# Sheet1.net
KiCad netlist of a schematic drawn in Altium Designer
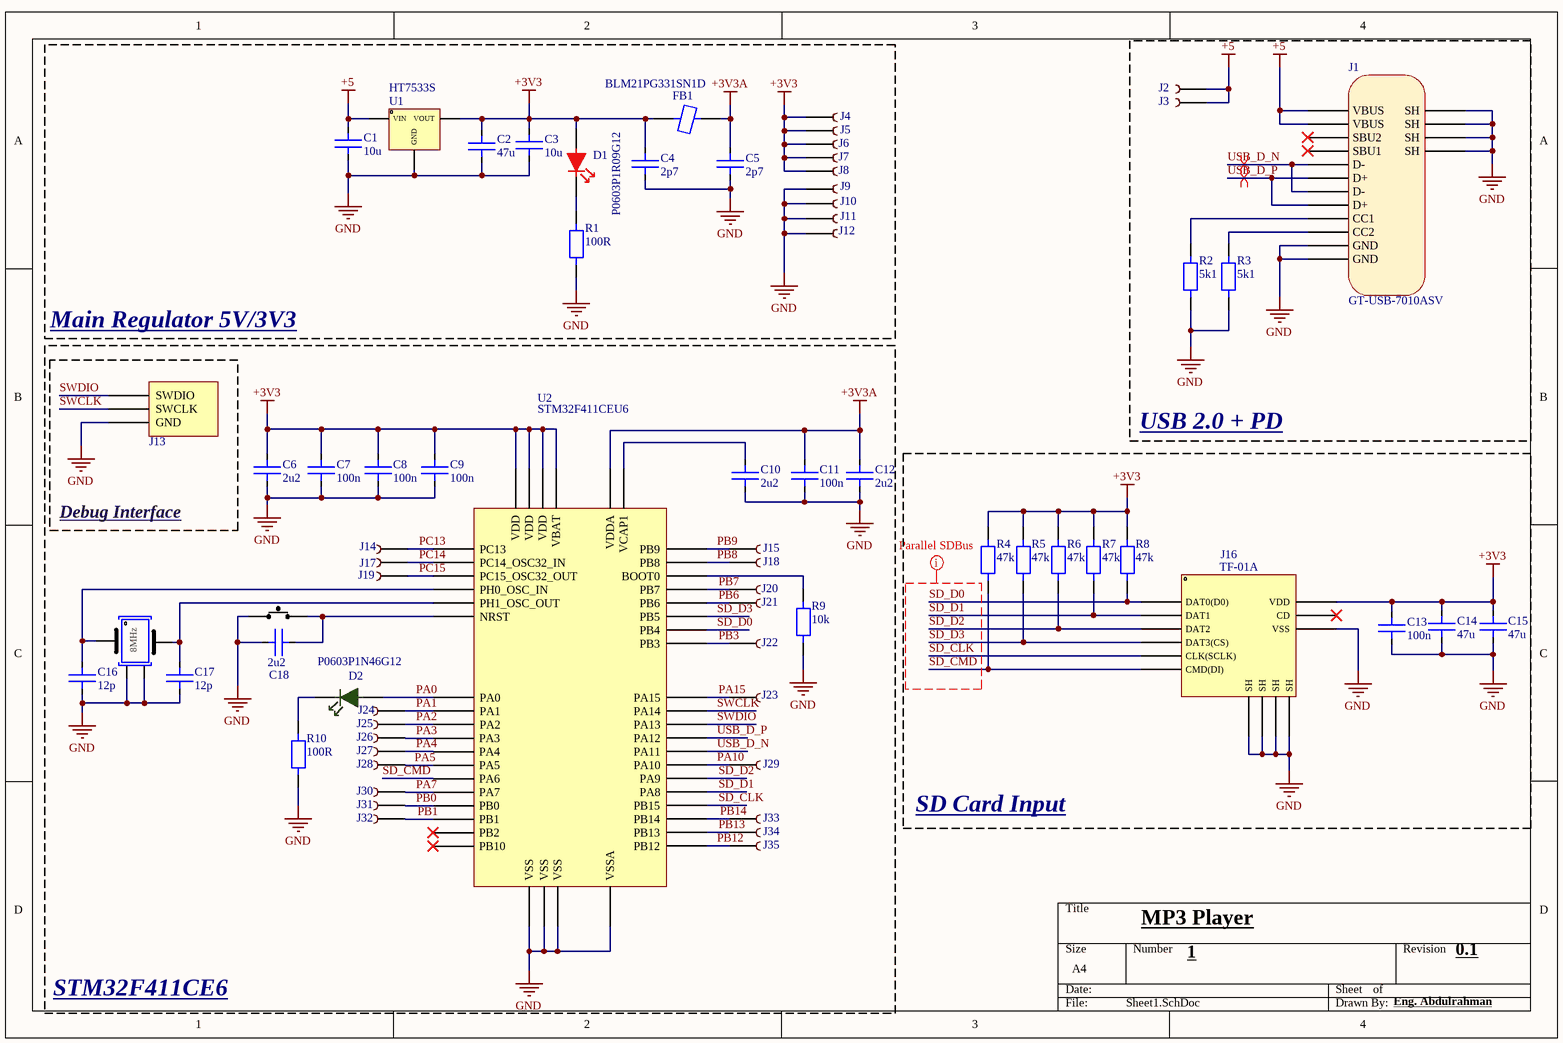
[diagram p0: Sheet1.SchDoc]

(export (version "E")
  (design (tool "Eeschema 10.0.6"))
  (components
    (comp (ref "C1")
      (value "10u")
      (footprint "CAP_MLCC_0805")
      (description "Multilayer  Ceramic Capacitor")
      (libsource (lib "conics_libs") (part "Cap MLCC 0805"))
    )
    (comp (ref "C2")
      (value "47u")
      (footprint "CAP_MLCC_0805")
      (description "Multilayer  Ceramic Capacitor")
      (libsource (lib "conics_libs") (part "Cap MLCC 0805"))
    )
    (comp (ref "C3")
      (value "10u")
      (footprint "CAP_MLCC_0805")
      (description "Multilayer  Ceramic Capacitor")
      (libsource (lib "conics_libs") (part "Cap MLCC 0805"))
    )
    (comp (ref "C4")
      (value "2p7")
      (footprint "CAP_MLCC_0402")
      (description "Multilayer  Ceramic Capacitor")
      (libsource (lib "conics_libs") (part "Cap MLCC 0402"))
    )
    (comp (ref "C5")
      (value "2p7")
      (footprint "CAP_MLCC_0402")
      (description "Multilayer  Ceramic Capacitor")
      (libsource (lib "conics_libs") (part "Cap MLCC 0402"))
    )
    (comp (ref "C6")
      (value "2u2")
      (footprint "CAP_MLCC_0402")
      (description "Multilayer  Ceramic Capacitor")
      (libsource (lib "conics_libs") (part "Cap MLCC 0402"))
    )
    (comp (ref "C7")
      (value "100n")
      (footprint "CAP_MLCC_0402")
      (description "Multilayer  Ceramic Capacitor")
      (libsource (lib "conics_libs") (part "Cap MLCC 0402"))
    )
    (comp (ref "C8")
      (value "100n")
      (footprint "CAP_MLCC_0402")
      (description "Multilayer  Ceramic Capacitor")
      (libsource (lib "conics_libs") (part "Cap MLCC 0402"))
    )
    (comp (ref "C9")
      (value "100n")
      (footprint "CAP_MLCC_0402")
      (description "Multilayer  Ceramic Capacitor")
      (libsource (lib "conics_libs") (part "Cap MLCC 0402"))
    )
    (comp (ref "C10")
      (value "2u2")
      (footprint "CAP_MLCC_0402")
      (description "Multilayer  Ceramic Capacitor")
      (libsource (lib "conics_libs") (part "Cap MLCC 0402"))
    )
    (comp (ref "C11")
      (value "100n")
      (footprint "CAP_MLCC_0402")
      (description "Multilayer  Ceramic Capacitor")
      (libsource (lib "conics_libs") (part "Cap MLCC 0402"))
    )
    (comp (ref "C12")
      (value "2u2")
      (footprint "CAP_MLCC_0402")
      (description "Multilayer  Ceramic Capacitor")
      (libsource (lib "conics_libs") (part "Cap MLCC 0402"))
    )
    (comp (ref "C13")
      (value "100n")
      (footprint "CAP_MLCC_0402")
      (description "Multilayer  Ceramic Capacitor")
      (libsource (lib "conics_libs") (part "Cap MLCC 0402"))
    )
    (comp (ref "C14")
      (value "47u")
      (footprint "CAP_MLCC_0805")
      (description "Multilayer  Ceramic Capacitor")
      (libsource (lib "conics_libs") (part "Cap MLCC 0805"))
    )
    (comp (ref "C15")
      (value "47u")
      (footprint "CAP_MLCC_0805")
      (description "Multilayer  Ceramic Capacitor")
      (libsource (lib "conics_libs") (part "Cap MLCC 0805"))
    )
    (comp (ref "C16")
      (value "12p")
      (footprint "CAP_MLCC_0402")
      (description "Multilayer  Ceramic Capacitor")
      (libsource (lib "conics_libs") (part "Cap MLCC 0402"))
    )
    (comp (ref "C17")
      (value "12p")
      (footprint "CAP_MLCC_0402")
      (description "Multilayer  Ceramic Capacitor")
      (libsource (lib "conics_libs") (part "Cap MLCC 0402"))
    )
    (comp (ref "C18")
      (value "2u2")
      (footprint "CAP_MLCC_0402")
      (description "Multilayer  Ceramic Capacitor")
      (libsource (lib "conics_libs") (part "Cap MLCC 0402"))
    )
    (comp (ref "D1")
      (value "P0603P1R09G12")
      (footprint "LED_0603")
      (description "20mA 350mcd 621nm Red 2V 0603 LED Indication - Discrete ROHS")
      (libsource (lib "conics_libs") (part "Diode LED R"))
    )
    (comp (ref "D2")
      (value "P0603P1N46G12")
      (footprint "LED_0603")
      (description "1200mcd 518nm~524nm Green 3V 0603 LED Indication - Discrete ROHS")
      (libsource (lib "conics_libs") (part "Diode LED G"))
    )
    (comp (ref "FB1")
      (value "BLM21PG331SN1D")
      (footprint "FBEAD_0805")
      (description "70mΩ ±25% 330Ω@100MHz 0805 Ferrite Beads and Chips RoHS")
      (libsource (lib "conics_libs") (part "Filter Ferrite Bead 0805"))
    )
    (comp (ref "J1")
      (value "GT-USB-7010ASV")
      (footprint "CONN_CH_USB_SMD_USB")
      (description "USB 2.0 1 16P -40℃~+85℃ Type-C SMD USB, DVI, HDMI Connector Assemblies ROHS")
      (libsource (lib "conics_libs") (part "Connector USB-C CH"))
    )
    (comp (ref "J2")
      (value "Castellated Pad")
      (footprint "CPad")
      (libsource (lib "conics_libs") (part "Castellated Pad"))
    )
    (comp (ref "J3")
      (value "Castellated Pad")
      (footprint "CPad")
      (libsource (lib "conics_libs") (part "Castellated Pad"))
    )
    (comp (ref "J4")
      (value "Castellated Pad")
      (footprint "CPad")
      (libsource (lib "conics_libs") (part "Castellated Pad"))
    )
    (comp (ref "J5")
      (value "Castellated Pad")
      (footprint "CPad")
      (libsource (lib "conics_libs") (part "Castellated Pad"))
    )
    (comp (ref "J6")
      (value "Castellated Pad")
      (footprint "CPad")
      (libsource (lib "conics_libs") (part "Castellated Pad"))
    )
    (comp (ref "J7")
      (value "Castellated Pad")
      (footprint "CPad")
      (libsource (lib "conics_libs") (part "Castellated Pad"))
    )
    (comp (ref "J8")
      (value "Castellated Pad")
      (footprint "CPad")
      (libsource (lib "conics_libs") (part "Castellated Pad"))
    )
    (comp (ref "J9")
      (value "Castellated Pad")
      (footprint "CPad")
      (libsource (lib "conics_libs") (part "Castellated Pad"))
    )
    (comp (ref "J10")
      (value "Castellated Pad")
      (footprint "CPad")
      (libsource (lib "conics_libs") (part "Castellated Pad"))
    )
    (comp (ref "J11")
      (value "Castellated Pad")
      (footprint "CPad")
      (libsource (lib "conics_libs") (part "Castellated Pad"))
    )
    (comp (ref "J12")
      (value "Castellated Pad")
      (footprint "CPad")
      (libsource (lib "conics_libs") (part "Castellated Pad"))
    )
    (comp (ref "J13")
      (value "DAP SWD")
      (footprint "CONN_JST_3P")
      (description "Connector Header 3 position 1mm Pitch 1A Surface Mount,Vertical -25℃~+85℃")
      (libsource (lib "conics_libs") (part "DAP SWD"))
    )
    (comp (ref "J14")
      (value "Castellated Pad")
      (footprint "CPad")
      (libsource (lib "conics_libs") (part "Castellated Pad"))
    )
    (comp (ref "J15")
      (value "Castellated Pad")
      (footprint "CPad")
      (libsource (lib "conics_libs") (part "Castellated Pad"))
    )
    (comp (ref "J16")
      (value "TF-01A")
      (footprint "CONN_CH_SMD_SD_CARD")
      (description "Push-Push 1.85mm Connector and Ejector MicroSD Card (TF Card) SMD PC Card Sockets ROHS")
      (libsource (lib "conics_libs") (part "Connector SD Card CH"))
    )
    (comp (ref "J17")
      (value "Castellated Pad")
      (footprint "CPad")
      (libsource (lib "conics_libs") (part "Castellated Pad"))
    )
    (comp (ref "J18")
      (value "Castellated Pad")
      (footprint "CPad")
      (libsource (lib "conics_libs") (part "Castellated Pad"))
    )
    (comp (ref "J19")
      (value "Castellated Pad")
      (footprint "CPad")
      (libsource (lib "conics_libs") (part "Castellated Pad"))
    )
    (comp (ref "J20")
      (value "Castellated Pad")
      (footprint "CPad")
      (libsource (lib "conics_libs") (part "Castellated Pad"))
    )
    (comp (ref "J21")
      (value "Castellated Pad")
      (footprint "CPad")
      (libsource (lib "conics_libs") (part "Castellated Pad"))
    )
    (comp (ref "J22")
      (value "Castellated Pad")
      (footprint "CPad")
      (libsource (lib "conics_libs") (part "Castellated Pad"))
    )
    (comp (ref "J23")
      (value "Castellated Pad")
      (footprint "CPad")
      (libsource (lib "conics_libs") (part "Castellated Pad"))
    )
    (comp (ref "J24")
      (value "Castellated Pad")
      (footprint "CPad")
      (libsource (lib "conics_libs") (part "Castellated Pad"))
    )
    (comp (ref "J25")
      (value "Castellated Pad")
      (footprint "CPad")
      (libsource (lib "conics_libs") (part "Castellated Pad"))
    )
    (comp (ref "J26")
      (value "Castellated Pad")
      (footprint "CPad")
      (libsource (lib "conics_libs") (part "Castellated Pad"))
    )
    (comp (ref "J27")
      (value "Castellated Pad")
      (footprint "CPad")
      (libsource (lib "conics_libs") (part "Castellated Pad"))
    )
    (comp (ref "J28")
      (value "Castellated Pad")
      (footprint "CPad")
      (libsource (lib "conics_libs") (part "Castellated Pad"))
    )
    (comp (ref "J29")
      (value "Castellated Pad")
      (footprint "CPad")
      (libsource (lib "conics_libs") (part "Castellated Pad"))
    )
    (comp (ref "J30")
      (value "Castellated Pad")
      (footprint "CPad")
      (libsource (lib "conics_libs") (part "Castellated Pad"))
    )
    (comp (ref "J31")
      (value "Castellated Pad")
      (footprint "CPad")
      (libsource (lib "conics_libs") (part "Castellated Pad"))
    )
    (comp (ref "J32")
      (value "Castellated Pad")
      (footprint "CPad")
      (libsource (lib "conics_libs") (part "Castellated Pad"))
    )
    (comp (ref "J33")
      (value "Castellated Pad")
      (footprint "CPad")
      (libsource (lib "conics_libs") (part "Castellated Pad"))
    )
    (comp (ref "J34")
      (value "Castellated Pad")
      (footprint "CPad")
      (libsource (lib "conics_libs") (part "Castellated Pad"))
    )
    (comp (ref "J35")
      (value "Castellated Pad")
      (footprint "CPad")
      (libsource (lib "conics_libs") (part "Castellated Pad"))
    )
    (comp (ref "R1")
      (value "100R")
      (footprint "RES_SMD_0402")
      (description "General Purpose SMD Carbon Resistor")
      (libsource (lib "conics_libs") (part "Resistor 0402"))
    )
    (comp (ref "R2")
      (value "5k1")
      (footprint "RES_SMD_0402")
      (description "General Purpose SMD Carbon Resistor")
      (libsource (lib "conics_libs") (part "Resistor 0402"))
    )
    (comp (ref "R3")
      (value "5k1")
      (footprint "RES_SMD_0402")
      (description "General Purpose SMD Carbon Resistor")
      (libsource (lib "conics_libs") (part "Resistor 0402"))
    )
    (comp (ref "R4")
      (value "47k")
      (footprint "RES_SMD_0402")
      (description "General Purpose SMD Carbon Resistor")
      (libsource (lib "conics_libs") (part "Resistor 0402"))
    )
    (comp (ref "R5")
      (value "47k")
      (footprint "RES_SMD_0402")
      (description "General Purpose SMD Carbon Resistor")
      (libsource (lib "conics_libs") (part "Resistor 0402"))
    )
    (comp (ref "R6")
      (value "47k")
      (footprint "RES_SMD_0402")
      (description "General Purpose SMD Carbon Resistor")
      (libsource (lib "conics_libs") (part "Resistor 0402"))
    )
    (comp (ref "R7")
      (value "47k")
      (footprint "RES_SMD_0402")
      (description "General Purpose SMD Carbon Resistor")
      (libsource (lib "conics_libs") (part "Resistor 0402"))
    )
    (comp (ref "R8")
      (value "47k")
      (footprint "RES_SMD_0402")
      (description "General Purpose SMD Carbon Resistor")
      (libsource (lib "conics_libs") (part "Resistor 0402"))
    )
    (comp (ref "R9")
      (value "10k")
      (footprint "RES_SMD_0402")
      (description "General Purpose SMD Carbon Resistor")
      (libsource (lib "conics_libs") (part "Resistor 0402"))
    )
    (comp (ref "R10")
      (value "100R")
      (footprint "RES_SMD_0402")
      (description "General Purpose SMD Carbon Resistor")
      (libsource (lib "conics_libs") (part "Resistor 0402"))
    )
    (comp (ref "SW1")
      (value "TS-1088-AR02016")
      (footprint "SW_SMD_SPST")
      (description "Without Bracket 4mm 12V 3mm Round Button SPST 50mA SMD,4x3mm Tactile Switches ROHS")
      (libsource (lib "conics_libs") (part "Switch SMD SPST"))
    )
    (comp (ref "U1")
      (value "HT7533S")
      (footprint "HT7533S_SOT23")
      (description "Linear Voltage Regulator IC Positive Fixed 1 Output 100mA SOT-23")
      (libsource (lib "conics_libs") (part "Regulator LDO HT7533S"))
    )
    (comp (ref "U2")
      (value "STM32F411CEU6")
      (footprint "STM32F411CEU6_QFPN48")
      (description "ARM Cortex-M4 32 Bit 100MHz 36 UFQFPN-48(7x7) Microcontrollers RoHS")
      (libsource (lib "conics_libs") (part "MCU STM32F411CEU6"))
    )
    (comp (ref "X1")
      (value "XC32M4-8.000-F12LJDT")
      (footprint "XTAL_SMD_HCL")
      (description "Crystal Oscillator 12pF SMD3225-4P Crystals RoHS")
      (libsource (lib "conics_libs") (part "Crystal SMD 8MHz"))
    )
  )
  (nets
    (net (code "1") (name "+3V3") (class "Default")
      (node (ref "C13") (pin "2") (pintype "passive"))
      (node (ref "C14") (pin "2") (pintype "passive"))
      (node (ref "C15") (pin "2") (pintype "passive"))
      (node (ref "C2") (pin "2") (pintype "passive"))
      (node (ref "C3") (pin "2") (pintype "passive"))
      (node (ref "C4") (pin "2") (pintype "passive"))
      (node (ref "C6") (pin "2") (pintype "passive"))
      (node (ref "C7") (pin "2") (pintype "passive"))
      (node (ref "C8") (pin "2") (pintype "passive"))
      (node (ref "C9") (pin "2") (pintype "passive"))
      (node (ref "D1") (pin "2") (pintype "passive"))
      (node (ref "FB1") (pin "1") (pintype "passive"))
      (node (ref "J16") (pin "4") (pinfunction "VDD_4") (pintype "passive"))
      (node (ref "J4") (pin "1") (pintype "passive"))
      (node (ref "J5") (pin "1") (pintype "passive"))
      (node (ref "J6") (pin "1") (pintype "passive"))
      (node (ref "J7") (pin "1") (pintype "passive"))
      (node (ref "J8") (pin "1") (pintype "passive"))
      (node (ref "R4") (pin "2") (pintype "passive"))
      (node (ref "R5") (pin "2") (pintype "passive"))
      (node (ref "R6") (pin "2") (pintype "passive"))
      (node (ref "R7") (pin "2") (pintype "passive"))
      (node (ref "R8") (pin "2") (pintype "passive"))
      (node (ref "U1") (pin "3") (pinfunction "VOUT_3") (pintype "passive"))
      (node (ref "U2") (pin "1") (pinfunction "VBAT_1") (pintype "passive"))
      (node (ref "U2") (pin "24") (pinfunction "VDD_24") (pintype "passive"))
      (node (ref "U2") (pin "36") (pinfunction "VDD_36") (pintype "passive"))
      (node (ref "U2") (pin "48") (pinfunction "VDD_48") (pintype "passive"))
    )
    (net (code "2") (name "+3V3A") (class "Default")
      (node (ref "C11") (pin "2") (pintype "passive"))
      (node (ref "C12") (pin "2") (pintype "passive"))
      (node (ref "C5") (pin "2") (pintype "passive"))
      (node (ref "FB1") (pin "2") (pintype "passive"))
      (node (ref "U2") (pin "9") (pinfunction "VDDA_9") (pintype "passive"))
    )
    (net (code "3") (name "+5") (class "Default")
      (node (ref "C1") (pin "2") (pintype "passive"))
      (node (ref "J1") (pin "1") (pinfunction "VBUS_1") (pintype "passive"))
      (node (ref "J1") (pin "2") (pinfunction "VBUS_2") (pintype "passive"))
      (node (ref "J2") (pin "1") (pintype "passive"))
      (node (ref "J3") (pin "1") (pintype "passive"))
      (node (ref "U1") (pin "2") (pinfunction "VIN_2") (pintype "passive"))
    )
    (net (code "4") (name "/PA0") (class "Default")
      (node (ref "D2") (pin "2") (pintype "passive"))
      (node (ref "U2") (pin "10") (pinfunction "PA0_10") (pintype "passive"))
    )
    (net (code "5") (name "/PA1") (class "Default")
      (node (ref "J24") (pin "1") (pintype "passive"))
      (node (ref "U2") (pin "11") (pinfunction "PA1_11") (pintype "passive"))
    )
    (net (code "6") (name "/PA2") (class "Default")
      (node (ref "J25") (pin "1") (pintype "passive"))
      (node (ref "U2") (pin "12") (pinfunction "PA2_12") (pintype "passive"))
    )
    (net (code "7") (name "/PA3") (class "Default")
      (node (ref "J26") (pin "1") (pintype "passive"))
      (node (ref "U2") (pin "13") (pinfunction "PA3_13") (pintype "passive"))
    )
    (net (code "8") (name "/PA4") (class "Default")
      (node (ref "J27") (pin "1") (pintype "passive"))
      (node (ref "U2") (pin "14") (pinfunction "PA4_14") (pintype "passive"))
    )
    (net (code "9") (name "/PA5") (class "Default")
      (node (ref "J28") (pin "1") (pintype "passive"))
      (node (ref "U2") (pin "15") (pinfunction "PA5_15") (pintype "passive"))
    )
    (net (code "10") (name "/PA7") (class "Default")
      (node (ref "J30") (pin "1") (pintype "passive"))
      (node (ref "U2") (pin "17") (pinfunction "PA7_17") (pintype "passive"))
    )
    (net (code "11") (name "/PA10") (class "Default")
      (node (ref "J29") (pin "1") (pintype "passive"))
      (node (ref "U2") (pin "31") (pinfunction "PA10_31") (pintype "passive"))
    )
    (net (code "12") (name "/PA15") (class "Default")
      (node (ref "J23") (pin "1") (pintype "passive"))
      (node (ref "U2") (pin "38") (pinfunction "PA15_38") (pintype "passive"))
    )
    (net (code "13") (name "/PB0") (class "Default")
      (node (ref "J31") (pin "1") (pintype "passive"))
      (node (ref "U2") (pin "18") (pinfunction "PB0_18") (pintype "passive"))
    )
    (net (code "14") (name "/PB1") (class "Default")
      (node (ref "J32") (pin "1") (pintype "passive"))
      (node (ref "U2") (pin "19") (pinfunction "PB1_19") (pintype "passive"))
    )
    (net (code "15") (name "/PB3") (class "Default")
      (node (ref "J22") (pin "1") (pintype "passive"))
      (node (ref "U2") (pin "39") (pinfunction "PB3_39") (pintype "passive"))
    )
    (net (code "16") (name "/PB6") (class "Default")
      (node (ref "J21") (pin "1") (pintype "passive"))
      (node (ref "U2") (pin "42") (pinfunction "PB6_42") (pintype "passive"))
    )
    (net (code "17") (name "/PB7") (class "Default")
      (node (ref "J20") (pin "1") (pintype "passive"))
      (node (ref "U2") (pin "43") (pinfunction "PB7_43") (pintype "passive"))
    )
    (net (code "18") (name "/PB8") (class "Default")
      (node (ref "J18") (pin "1") (pintype "passive"))
      (node (ref "U2") (pin "45") (pinfunction "PB8_45") (pintype "passive"))
    )
    (net (code "19") (name "/PB9") (class "Default")
      (node (ref "J15") (pin "1") (pintype "passive"))
      (node (ref "U2") (pin "46") (pinfunction "PB9_46") (pintype "passive"))
    )
    (net (code "20") (name "/PB12") (class "Default")
      (node (ref "J35") (pin "1") (pintype "passive"))
      (node (ref "U2") (pin "25") (pinfunction "PB12_25") (pintype "passive"))
    )
    (net (code "21") (name "/PB13") (class "Default")
      (node (ref "J34") (pin "1") (pintype "passive"))
      (node (ref "U2") (pin "26") (pinfunction "PB13_26") (pintype "passive"))
    )
    (net (code "22") (name "/PB14") (class "Default")
      (node (ref "J33") (pin "1") (pintype "passive"))
      (node (ref "U2") (pin "27") (pinfunction "PB14_27") (pintype "passive"))
    )
    (net (code "23") (name "/PC13") (class "Default")
      (node (ref "J14") (pin "1") (pintype "passive"))
      (node (ref "U2") (pin "2") (pinfunction "PC13_2") (pintype "passive"))
    )
    (net (code "24") (name "/PC14") (class "Default")
      (node (ref "J17") (pin "1") (pintype "passive"))
      (node (ref "U2") (pin "3") (pinfunction "PC14_OSC32_IN_3") (pintype "passive"))
    )
    (net (code "25") (name "/PC15") (class "Default")
      (node (ref "J19") (pin "1") (pintype "passive"))
      (node (ref "U2") (pin "4") (pinfunction "PC15_OSC32_OUT_4") (pintype "passive"))
    )
    (net (code "26") (name "/SD_CLK") (class "Default")
      (node (ref "J16") (pin "5") (pinfunction "CLK(SCLK)_5") (pintype "passive"))
      (node (ref "U2") (pin "28") (pinfunction "PB15_28") (pintype "passive"))
    )
    (net (code "27") (name "/SD_CMD") (class "Default")
      (node (ref "J16") (pin "3") (pinfunction "CMD(DI)_3") (pintype "passive"))
      (node (ref "R4") (pin "1") (pintype "passive"))
      (node (ref "U2") (pin "16") (pinfunction "PA6_16") (pintype "passive"))
    )
    (net (code "28") (name "/SD_D0") (class "Default")
      (node (ref "J16") (pin "7") (pinfunction "DAT0(D0)_7") (pintype "passive"))
      (node (ref "R8") (pin "1") (pintype "passive"))
      (node (ref "U2") (pin "40") (pinfunction "PB4_40") (pintype "passive"))
    )
    (net (code "29") (name "/SD_D1") (class "Default")
      (node (ref "J16") (pin "8") (pinfunction "DAT1_8") (pintype "passive"))
      (node (ref "R7") (pin "1") (pintype "passive"))
      (node (ref "U2") (pin "29") (pinfunction "PA8_29") (pintype "passive"))
    )
    (net (code "30") (name "/SD_D2") (class "Default")
      (node (ref "J16") (pin "1") (pinfunction "DAT2_1") (pintype "passive"))
      (node (ref "R6") (pin "1") (pintype "passive"))
      (node (ref "U2") (pin "30") (pinfunction "PA9_30") (pintype "passive"))
    )
    (net (code "31") (name "/SD_D3") (class "Default")
      (node (ref "J16") (pin "2") (pinfunction "DAT3(CS)_2") (pintype "passive"))
      (node (ref "R5") (pin "1") (pintype "passive"))
      (node (ref "U2") (pin "41") (pinfunction "PB5_41") (pintype "passive"))
    )
    (net (code "32") (name "/SWCLK") (class "Default")
      (node (ref "J13") (pin "2") (pinfunction "SWCLK_2") (pintype "passive"))
      (node (ref "U2") (pin "37") (pinfunction "PA14_37") (pintype "passive"))
    )
    (net (code "33") (name "/SWDIO") (class "Default")
      (node (ref "J13") (pin "1") (pinfunction "SWDIO_1") (pintype "passive"))
      (node (ref "U2") (pin "34") (pinfunction "PA13_34") (pintype "passive"))
    )
    (net (code "34") (name "/USB_D_N") (class "Default")
      (node (ref "J1") (pin "5") (pinfunction "D-_5") (pintype "passive"))
      (node (ref "J1") (pin "7") (pinfunction "D-_7") (pintype "passive"))
      (node (ref "U2") (pin "32") (pinfunction "PA11_32") (pintype "passive"))
    )
    (net (code "35") (name "/USB_D_P") (class "Default")
      (node (ref "J1") (pin "6") (pinfunction "D+_6") (pintype "passive"))
      (node (ref "J1") (pin "8") (pinfunction "D+_8") (pintype "passive"))
      (node (ref "U2") (pin "33") (pinfunction "PA12_33") (pintype "passive"))
    )
    (net (code "36") (name "GND") (class "Default")
      (node (ref "C1") (pin "1") (pintype "passive"))
      (node (ref "C10") (pin "1") (pintype "passive"))
      (node (ref "C11") (pin "1") (pintype "passive"))
      (node (ref "C12") (pin "1") (pintype "passive"))
      (node (ref "C13") (pin "1") (pintype "passive"))
      (node (ref "C14") (pin "1") (pintype "passive"))
      (node (ref "C15") (pin "1") (pintype "passive"))
      (node (ref "C16") (pin "1") (pintype "passive"))
      (node (ref "C17") (pin "1") (pintype "passive"))
      (node (ref "C18") (pin "2") (pintype "passive"))
      (node (ref "C2") (pin "1") (pintype "passive"))
      (node (ref "C3") (pin "1") (pintype "passive"))
      (node (ref "C4") (pin "1") (pintype "passive"))
      (node (ref "C5") (pin "1") (pintype "passive"))
      (node (ref "C6") (pin "1") (pintype "passive"))
      (node (ref "C7") (pin "1") (pintype "passive"))
      (node (ref "C8") (pin "1") (pintype "passive"))
      (node (ref "C9") (pin "1") (pintype "passive"))
      (node (ref "J1") (pin "11") (pinfunction "GND_11") (pintype "passive"))
      (node (ref "J1") (pin "12") (pinfunction "GND_12") (pintype "passive"))
      (node (ref "J1") (pin "13") (pinfunction "SH_13") (pintype "passive"))
      (node (ref "J1") (pin "14") (pinfunction "SH_14") (pintype "passive"))
      (node (ref "J1") (pin "15") (pinfunction "SH_15") (pintype "passive"))
      (node (ref "J1") (pin "16") (pinfunction "SH_16") (pintype "passive"))
      (node (ref "J10") (pin "1") (pintype "passive"))
      (node (ref "J11") (pin "1") (pintype "passive"))
      (node (ref "J12") (pin "1") (pintype "passive"))
      (node (ref "J13") (pin "3") (pinfunction "GND_3") (pintype "passive"))
      (node (ref "J16") (pin "10") (pinfunction "SH_10") (pintype "passive"))
      (node (ref "J16") (pin "11") (pinfunction "SH_11") (pintype "passive"))
      (node (ref "J16") (pin "12") (pinfunction "SH_12") (pintype "passive"))
      (node (ref "J16") (pin "13") (pinfunction "SH_13") (pintype "passive"))
      (node (ref "J16") (pin "6") (pinfunction "VSS_6") (pintype "passive"))
      (node (ref "J9") (pin "1") (pintype "passive"))
      (node (ref "R1") (pin "2") (pintype "passive"))
      (node (ref "R10") (pin "1") (pintype "passive"))
      (node (ref "R2") (pin "1") (pintype "passive"))
      (node (ref "R3") (pin "1") (pintype "passive"))
      (node (ref "R9") (pin "1") (pintype "passive"))
      (node (ref "SW1") (pin "1") (pintype "passive"))
      (node (ref "U1") (pin "1") (pinfunction "GND_1") (pintype "passive"))
      (node (ref "U2") (pin "23") (pinfunction "VSS_23") (pintype "passive"))
      (node (ref "U2") (pin "35") (pinfunction "VSS_35") (pintype "passive"))
      (node (ref "U2") (pin "47") (pinfunction "VSS_47") (pintype "passive"))
      (node (ref "U2") (pin "8") (pinfunction "VSSA_8") (pintype "passive"))
      (node (ref "X1") (pin "2") (pintype "passive"))
      (node (ref "X1") (pin "4") (pintype "passive"))
    )
    (net (code "37") (name "Net-(D1-Pad1)") (class "Default")
      (node (ref "D1") (pin "1") (pintype "passive"))
      (node (ref "R1") (pin "1") (pintype "passive"))
    )
    (net (code "38") (name "Net-(D2-Pad1)") (class "Default")
      (node (ref "D2") (pin "1") (pintype "passive"))
      (node (ref "R10") (pin "2") (pintype "passive"))
    )
    (net (code "39") (name "Net-(J1-CC1)") (class "Default")
      (node (ref "J1") (pin "4") (pinfunction "CC1_4") (pintype "passive"))
      (node (ref "R2") (pin "2") (pintype "passive"))
    )
    (net (code "40") (name "Net-(J1-CC2)") (class "Default")
      (node (ref "J1") (pin "10") (pinfunction "CC2_10") (pintype "passive"))
      (node (ref "R3") (pin "2") (pintype "passive"))
    )
    (net (code "41") (name "Net-(U2-BOOT0)") (class "Default")
      (node (ref "R9") (pin "2") (pintype "passive"))
      (node (ref "U2") (pin "44") (pinfunction "BOOT0_44") (pintype "passive"))
    )
    (net (code "42") (name "Net-(U2-NRST)") (class "Default")
      (node (ref "C18") (pin "1") (pintype "passive"))
      (node (ref "SW1") (pin "2") (pintype "passive"))
      (node (ref "U2") (pin "7") (pinfunction "NRST_7") (pintype "passive"))
    )
    (net (code "43") (name "Net-(U2-PH0_OSC_IN)") (class "Default")
      (node (ref "C16") (pin "2") (pintype "passive"))
      (node (ref "U2") (pin "5") (pinfunction "PH0_OSC_IN_5") (pintype "passive"))
      (node (ref "X1") (pin "1") (pintype "passive"))
    )
    (net (code "44") (name "Net-(U2-PH1_OSC_OUT)") (class "Default")
      (node (ref "C17") (pin "2") (pintype "passive"))
      (node (ref "U2") (pin "6") (pinfunction "PH1_OSC_OUT_6") (pintype "passive"))
      (node (ref "X1") (pin "3") (pintype "passive"))
    )
    (net (code "45") (name "Net-(U2-VCAP1)") (class "Default")
      (node (ref "C10") (pin "2") (pintype "passive"))
      (node (ref "U2") (pin "22") (pinfunction "VCAP1_22") (pintype "passive"))
    )
    (net (code "46") (name "unconnected-(J1-SBU1-Pad9)") (class "Default")
      (node (ref "J1") (pin "9") (pinfunction "SBU1_9") (pintype "passive+no_connect"))
    )
    (net (code "47") (name "unconnected-(J1-SBU2-Pad3)") (class "Default")
      (node (ref "J1") (pin "3") (pinfunction "SBU2_3") (pintype "passive+no_connect"))
    )
    (net (code "48") (name "unconnected-(J16-CD-Pad9)") (class "Default")
      (node (ref "J16") (pin "9") (pinfunction "CD_9") (pintype "passive+no_connect"))
    )
    (net (code "49") (name "unconnected-(U2-PB2-Pad20)") (class "Default")
      (node (ref "U2") (pin "20") (pinfunction "PB2_20") (pintype "passive+no_connect"))
    )
    (net (code "50") (name "unconnected-(U2-PB10-Pad21)") (class "Default")
      (node (ref "U2") (pin "21") (pinfunction "PB10_21") (pintype "passive+no_connect"))
    )
  )
)
